# mach_nguon_sch.net
KiCad netlist of a schematic drawn in Altium Designer
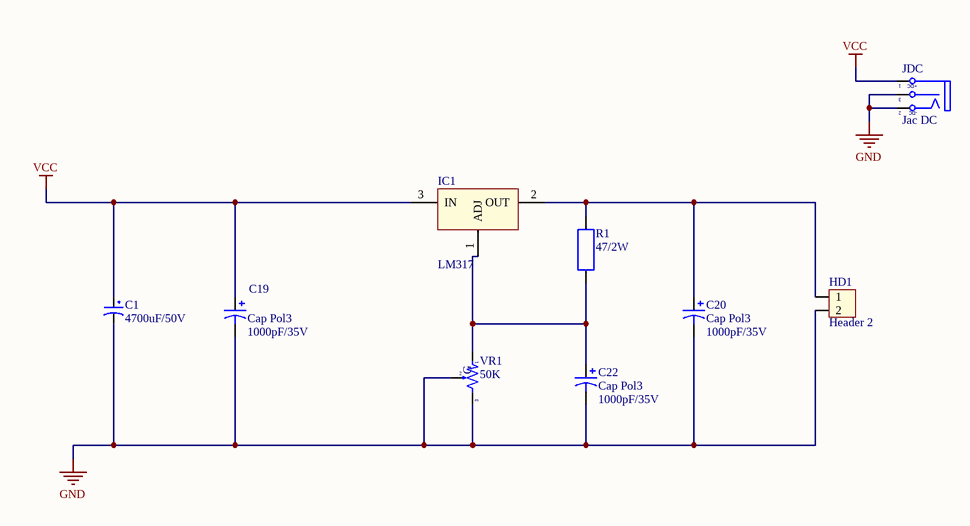
[diagram p0: mach nguon sch.SchDoc]

(export (version "E")
  (design (tool "Eeschema 10.0.6"))
  (components
    (comp (ref "C1")
      (value "4700uF/50V")
      (footprint "CP4/8.5")
      (description "Cap 4700uF/50V")
      (libsource (lib "syhaunguyen") (part "CP7"))
    )
    (comp (ref "C19")
      (value "Cap Pol3")
      (footprint "CP2/5")
      (description "Polarized Capacitor (Surface Mount)")
      (fields (field (name "ALTIUM_VALUE") "1000pF/35V") (field (name "PUBLISHER") "Altium Limited"))
      (libsource (lib "syhaunguyen") (part "Cap Pol3_1"))
    )
    (comp (ref "C20")
      (value "Cap Pol3")
      (footprint "CP2/5")
      (description "Polarized Capacitor (Surface Mount)")
      (fields (field (name "ALTIUM_VALUE") "1000pF/35V") (field (name "PUBLISHER") "Altium Limited"))
      (libsource (lib "syhaunguyen") (part "Cap Pol3_2"))
    )
    (comp (ref "C22")
      (value "Cap Pol3")
      (footprint "CP2/5")
      (description "Polarized Capacitor (Surface Mount)")
      (fields (field (name "ALTIUM_VALUE") "1000pF/35V") (field (name "PUBLISHER") "Altium Limited"))
      (libsource (lib "syhaunguyen") (part "Cap Pol3_3"))
    )
    (comp (ref "HD1")
      (value "Header 2")
      (footprint "HED2")
      (description "Header 2 (Green)")
      (libsource (lib "syhaunguyen") (part "Hed2"))
    )
    (comp (ref "IC1")
      (value "LM317")
      (footprint "QTO-220")
      (description "Adj Voltage +1.2 -> +37V")
      (libsource (lib "syhaunguyen") (part "LM317"))
    )
    (comp (ref "JDC")
      (value "Jac DC")
      (footprint "DC-IN")
      (description "Jac DC input")
      (libsource (lib "syhaunguyen") (part "DCIN"))
    )
    (comp (ref "R1")
      (value "47/2W")
      (footprint "R2W")
      (description "Resistor 2W")
      (libsource (lib "syhaunguyen") (part "R2W"))
    )
    (comp (ref "VR1")
      (value "50K")
      (footprint "VR-S1")
      (description "Var Resistor")
      (libsource (lib "LIBRARY") (part "VR-S"))
    )
  )
  (nets
    (net (code "1") (name "GND") (class "Default")
      (node (ref "C1") (pin "2") (pinfunction "2_2") (pintype "passive"))
      (node (ref "C19") (pin "2") (pinfunction "2_2") (pintype "passive"))
      (node (ref "C20") (pin "2") (pinfunction "2_2") (pintype "passive"))
      (node (ref "C22") (pin "2") (pinfunction "2_2") (pintype "passive"))
      (node (ref "HD1") (pin "2") (pinfunction "2_2") (pintype "passive"))
      (node (ref "JDC") (pin "2") (pinfunction "TN_2") (pintype "passive"))
      (node (ref "JDC") (pin "3") (pinfunction "S_3") (pintype "power_in"))
      (node (ref "VR1") (pin "2") (pinfunction "2_2") (pintype "passive"))
      (node (ref "VR1") (pin "3") (pinfunction "3_3") (pintype "passive"))
    )
    (net (code "2") (name "Net-(IC1-ADJ)") (class "Default")
      (node (ref "C22") (pin "1") (pinfunction "1_1") (pintype "passive"))
      (node (ref "IC1") (pin "1") (pinfunction "ADJ_1") (pintype "passive"))
      (node (ref "R1") (pin "1") (pinfunction "1_1") (pintype "passive"))
      (node (ref "VR1") (pin "1") (pinfunction "1_1") (pintype "passive"))
    )
    (net (code "3") (name "Net-(IC1-OUT)") (class "Default")
      (node (ref "C20") (pin "1") (pinfunction "1_1") (pintype "passive"))
      (node (ref "HD1") (pin "1") (pinfunction "1_1") (pintype "passive"))
      (node (ref "IC1") (pin "2") (pinfunction "OUT_2") (pintype "passive"))
      (node (ref "R1") (pin "2") (pinfunction "2_2") (pintype "passive"))
    )
    (net (code "4") (name "VCC") (class "Default")
      (node (ref "C1") (pin "1") (pinfunction "1_1") (pintype "passive"))
      (node (ref "C19") (pin "1") (pinfunction "1_1") (pintype "passive"))
      (node (ref "IC1") (pin "3") (pinfunction "IN_3") (pintype "passive"))
      (node (ref "JDC") (pin "1") (pinfunction "T_1") (pintype "passive"))
    )
  )
)
